# TJMakes_Hub.net
KiCad netlist of a schematic drawn in EasyEDA Pro
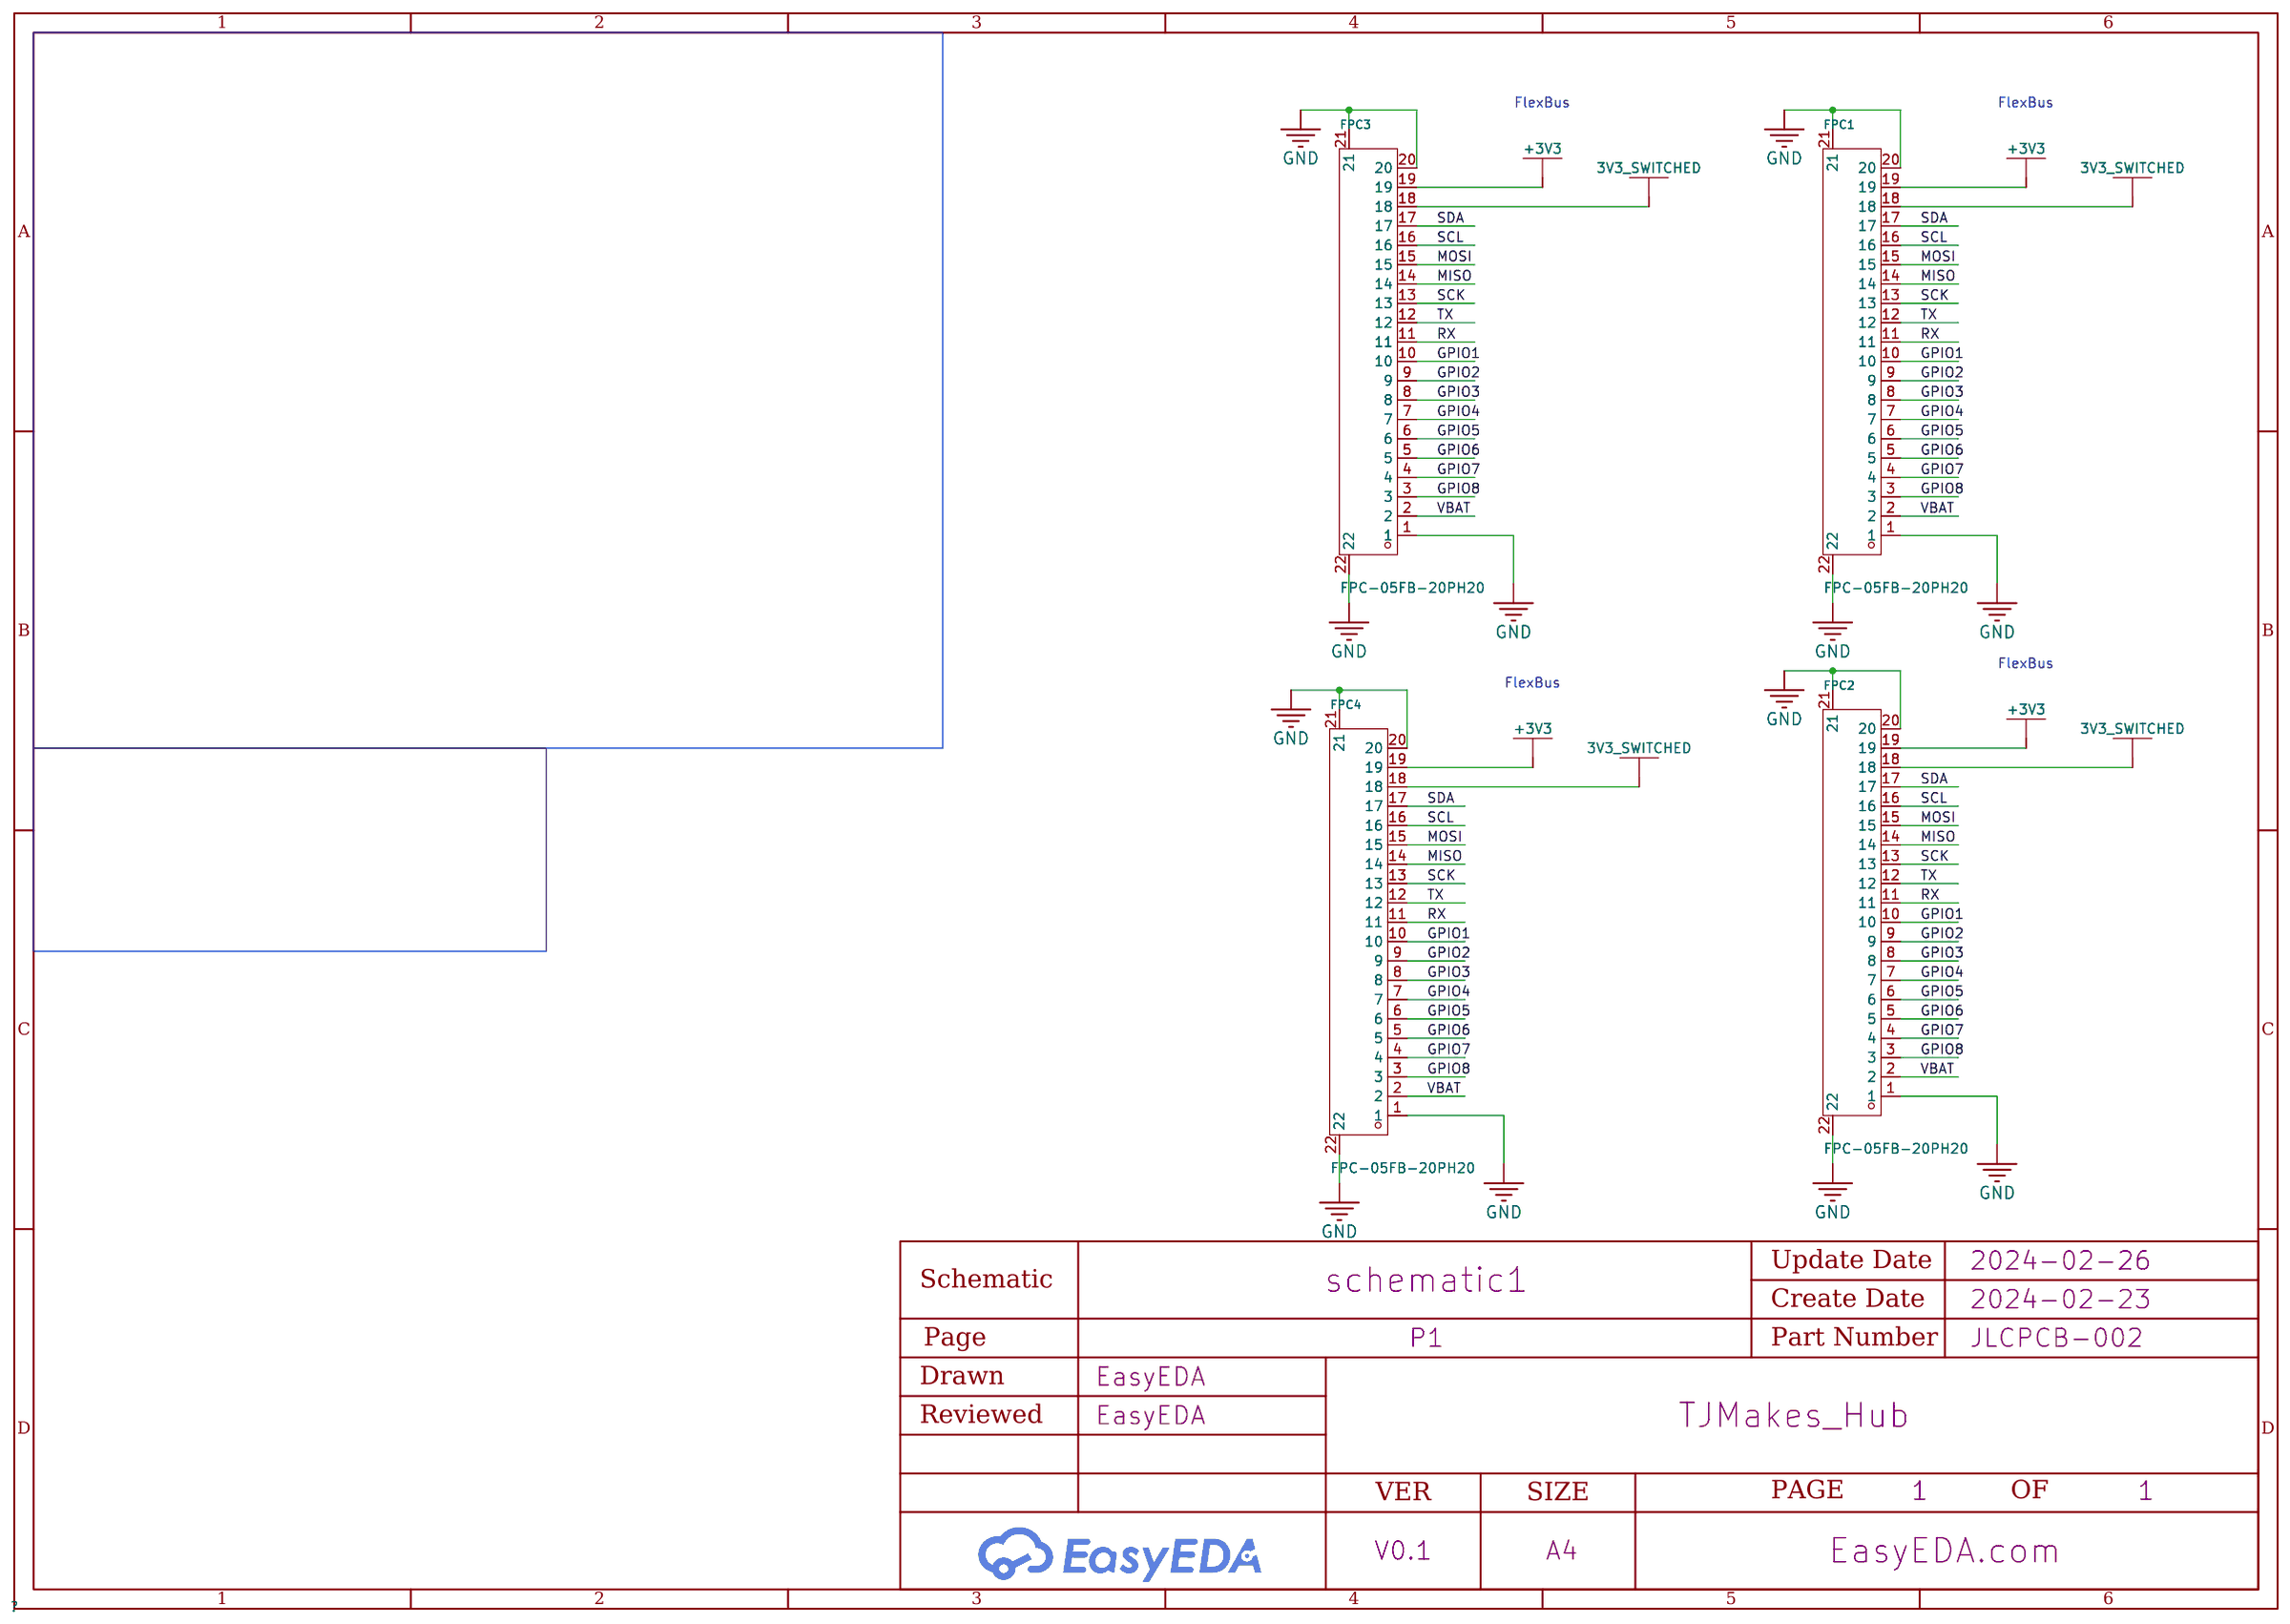
[diagram p0: schematic sheet]

(export (version "E")
  (design (tool "Eeschema 10.0.6"))
  (components
    (comp (ref "FPC1")
      (value "FPC-05FB-20PH20")
      (footprint "easyedapro:FPC-SMD_20P-P0.50_FPC-05FB-20PH20")
      (fields (field (name "Manufacturer") "XUNPU(讯普)"))
      (libsource (lib "easyedapro") (part "FPC-05FB-20PH20"))
    )
    (comp (ref "FPC2")
      (value "FPC-05FB-20PH20")
      (footprint "easyedapro:FPC-SMD_20P-P0.50_FPC-05FB-20PH20")
      (fields (field (name "Manufacturer") "XUNPU(讯普)"))
      (libsource (lib "easyedapro") (part "FPC-05FB-20PH20"))
    )
    (comp (ref "FPC3")
      (value "FPC-05FB-20PH20")
      (footprint "easyedapro:FPC-SMD_20P-P0.50_FPC-05FB-20PH20")
      (fields (field (name "Manufacturer") "XUNPU(讯普)"))
      (libsource (lib "easyedapro") (part "FPC-05FB-20PH20"))
    )
    (comp (ref "FPC4")
      (value "FPC-05FB-20PH20")
      (footprint "easyedapro:FPC-SMD_20P-P0.50_FPC-05FB-20PH20")
      (fields (field (name "Manufacturer") "XUNPU(讯普)"))
      (libsource (lib "easyedapro") (part "FPC-05FB-20PH20"))
    )
  )
  (nets
    (net (code "1") (name "+3V3") (class "Default")
      (node (ref "FPC1") (pin "19") (pinfunction "19_19") (pintype "input"))
      (node (ref "FPC2") (pin "19") (pinfunction "19_19") (pintype "input"))
      (node (ref "FPC3") (pin "19") (pinfunction "19_19") (pintype "input"))
      (node (ref "FPC4") (pin "19") (pinfunction "19_19") (pintype "input"))
    )
    (net (code "2") (name "/GPIO1") (class "Default")
      (node (ref "FPC1") (pin "10") (pinfunction "10_10") (pintype "input"))
      (node (ref "FPC2") (pin "10") (pinfunction "10_10") (pintype "input"))
      (node (ref "FPC3") (pin "10") (pinfunction "10_10") (pintype "input"))
      (node (ref "FPC4") (pin "10") (pinfunction "10_10") (pintype "input"))
    )
    (net (code "3") (name "/GPIO2") (class "Default")
      (node (ref "FPC1") (pin "9") (pinfunction "9_9") (pintype "input"))
      (node (ref "FPC2") (pin "9") (pinfunction "9_9") (pintype "input"))
      (node (ref "FPC3") (pin "9") (pinfunction "9_9") (pintype "input"))
      (node (ref "FPC4") (pin "9") (pinfunction "9_9") (pintype "input"))
    )
    (net (code "4") (name "/GPIO3") (class "Default")
      (node (ref "FPC1") (pin "8") (pinfunction "8_8") (pintype "input"))
      (node (ref "FPC2") (pin "8") (pinfunction "8_8") (pintype "input"))
      (node (ref "FPC3") (pin "8") (pinfunction "8_8") (pintype "input"))
      (node (ref "FPC4") (pin "8") (pinfunction "8_8") (pintype "input"))
    )
    (net (code "5") (name "/GPIO4") (class "Default")
      (node (ref "FPC1") (pin "7") (pinfunction "7_7") (pintype "input"))
      (node (ref "FPC2") (pin "7") (pinfunction "7_7") (pintype "input"))
      (node (ref "FPC3") (pin "7") (pinfunction "7_7") (pintype "input"))
      (node (ref "FPC4") (pin "7") (pinfunction "7_7") (pintype "input"))
    )
    (net (code "6") (name "/GPIO5") (class "Default")
      (node (ref "FPC1") (pin "6") (pinfunction "6_6") (pintype "input"))
      (node (ref "FPC2") (pin "6") (pinfunction "6_6") (pintype "input"))
      (node (ref "FPC3") (pin "6") (pinfunction "6_6") (pintype "input"))
      (node (ref "FPC4") (pin "6") (pinfunction "6_6") (pintype "input"))
    )
    (net (code "7") (name "/GPIO6") (class "Default")
      (node (ref "FPC1") (pin "5") (pinfunction "5_5") (pintype "input"))
      (node (ref "FPC2") (pin "5") (pinfunction "5_5") (pintype "input"))
      (node (ref "FPC3") (pin "5") (pinfunction "5_5") (pintype "input"))
      (node (ref "FPC4") (pin "5") (pinfunction "5_5") (pintype "input"))
    )
    (net (code "8") (name "/GPIO7") (class "Default")
      (node (ref "FPC1") (pin "4") (pinfunction "4_4") (pintype "input"))
      (node (ref "FPC2") (pin "4") (pinfunction "4_4") (pintype "input"))
      (node (ref "FPC3") (pin "4") (pinfunction "4_4") (pintype "input"))
      (node (ref "FPC4") (pin "4") (pinfunction "4_4") (pintype "input"))
    )
    (net (code "9") (name "/GPIO8") (class "Default")
      (node (ref "FPC1") (pin "3") (pinfunction "3_3") (pintype "input"))
      (node (ref "FPC2") (pin "3") (pinfunction "3_3") (pintype "input"))
      (node (ref "FPC3") (pin "3") (pinfunction "3_3") (pintype "input"))
      (node (ref "FPC4") (pin "3") (pinfunction "3_3") (pintype "input"))
    )
    (net (code "10") (name "/MISO") (class "Default")
      (node (ref "FPC1") (pin "14") (pinfunction "14_14") (pintype "input"))
      (node (ref "FPC2") (pin "14") (pinfunction "14_14") (pintype "input"))
      (node (ref "FPC3") (pin "14") (pinfunction "14_14") (pintype "input"))
      (node (ref "FPC4") (pin "14") (pinfunction "14_14") (pintype "input"))
    )
    (net (code "11") (name "/MOSI") (class "Default")
      (node (ref "FPC1") (pin "15") (pinfunction "15_15") (pintype "input"))
      (node (ref "FPC2") (pin "15") (pinfunction "15_15") (pintype "input"))
      (node (ref "FPC3") (pin "15") (pinfunction "15_15") (pintype "input"))
      (node (ref "FPC4") (pin "15") (pinfunction "15_15") (pintype "input"))
    )
    (net (code "12") (name "/RX") (class "Default")
      (node (ref "FPC1") (pin "11") (pinfunction "11_11") (pintype "input"))
      (node (ref "FPC2") (pin "11") (pinfunction "11_11") (pintype "input"))
      (node (ref "FPC3") (pin "11") (pinfunction "11_11") (pintype "input"))
      (node (ref "FPC4") (pin "11") (pinfunction "11_11") (pintype "input"))
    )
    (net (code "13") (name "/SCK") (class "Default")
      (node (ref "FPC1") (pin "13") (pinfunction "13_13") (pintype "input"))
      (node (ref "FPC2") (pin "13") (pinfunction "13_13") (pintype "input"))
      (node (ref "FPC3") (pin "13") (pinfunction "13_13") (pintype "input"))
      (node (ref "FPC4") (pin "13") (pinfunction "13_13") (pintype "input"))
    )
    (net (code "14") (name "/SCL") (class "Default")
      (node (ref "FPC1") (pin "16") (pinfunction "16_16") (pintype "input"))
      (node (ref "FPC2") (pin "16") (pinfunction "16_16") (pintype "input"))
      (node (ref "FPC3") (pin "16") (pinfunction "16_16") (pintype "input"))
      (node (ref "FPC4") (pin "16") (pinfunction "16_16") (pintype "input"))
    )
    (net (code "15") (name "/SDA") (class "Default")
      (node (ref "FPC1") (pin "17") (pinfunction "17_17") (pintype "input"))
      (node (ref "FPC2") (pin "17") (pinfunction "17_17") (pintype "input"))
      (node (ref "FPC3") (pin "17") (pinfunction "17_17") (pintype "input"))
      (node (ref "FPC4") (pin "17") (pinfunction "17_17") (pintype "input"))
    )
    (net (code "16") (name "/TX") (class "Default")
      (node (ref "FPC1") (pin "12") (pinfunction "12_12") (pintype "input"))
      (node (ref "FPC2") (pin "12") (pinfunction "12_12") (pintype "input"))
      (node (ref "FPC3") (pin "12") (pinfunction "12_12") (pintype "input"))
      (node (ref "FPC4") (pin "12") (pinfunction "12_12") (pintype "input"))
    )
    (net (code "17") (name "/VBAT") (class "Default")
      (node (ref "FPC1") (pin "2") (pinfunction "2_2") (pintype "input"))
      (node (ref "FPC2") (pin "2") (pinfunction "2_2") (pintype "input"))
      (node (ref "FPC3") (pin "2") (pinfunction "2_2") (pintype "input"))
      (node (ref "FPC4") (pin "2") (pinfunction "2_2") (pintype "input"))
    )
    (net (code "18") (name "3V3_SWITCHED") (class "Default")
      (node (ref "FPC1") (pin "18") (pinfunction "18_18") (pintype "input"))
      (node (ref "FPC2") (pin "18") (pinfunction "18_18") (pintype "input"))
      (node (ref "FPC3") (pin "18") (pinfunction "18_18") (pintype "input"))
      (node (ref "FPC4") (pin "18") (pinfunction "18_18") (pintype "input"))
    )
    (net (code "19") (name "GND") (class "Default")
      (node (ref "FPC1") (pin "1") (pinfunction "1_1") (pintype "input"))
      (node (ref "FPC1") (pin "20") (pinfunction "20_20") (pintype "input"))
      (node (ref "FPC1") (pin "21") (pinfunction "21_21") (pintype "input"))
      (node (ref "FPC1") (pin "22") (pinfunction "22_22") (pintype "input"))
      (node (ref "FPC2") (pin "1") (pinfunction "1_1") (pintype "input"))
      (node (ref "FPC2") (pin "20") (pinfunction "20_20") (pintype "input"))
      (node (ref "FPC2") (pin "21") (pinfunction "21_21") (pintype "input"))
      (node (ref "FPC2") (pin "22") (pinfunction "22_22") (pintype "input"))
      (node (ref "FPC3") (pin "1") (pinfunction "1_1") (pintype "input"))
      (node (ref "FPC3") (pin "20") (pinfunction "20_20") (pintype "input"))
      (node (ref "FPC3") (pin "21") (pinfunction "21_21") (pintype "input"))
      (node (ref "FPC3") (pin "22") (pinfunction "22_22") (pintype "input"))
      (node (ref "FPC4") (pin "1") (pinfunction "1_1") (pintype "input"))
      (node (ref "FPC4") (pin "20") (pinfunction "20_20") (pintype "input"))
      (node (ref "FPC4") (pin "21") (pinfunction "21_21") (pintype "input"))
      (node (ref "FPC4") (pin "22") (pinfunction "22_22") (pintype "input"))
    )
  )
)
